# ProPrj_tp4056_charger_2026-03-09.net
KiCad netlist of a schematic drawn in EasyEDA Pro
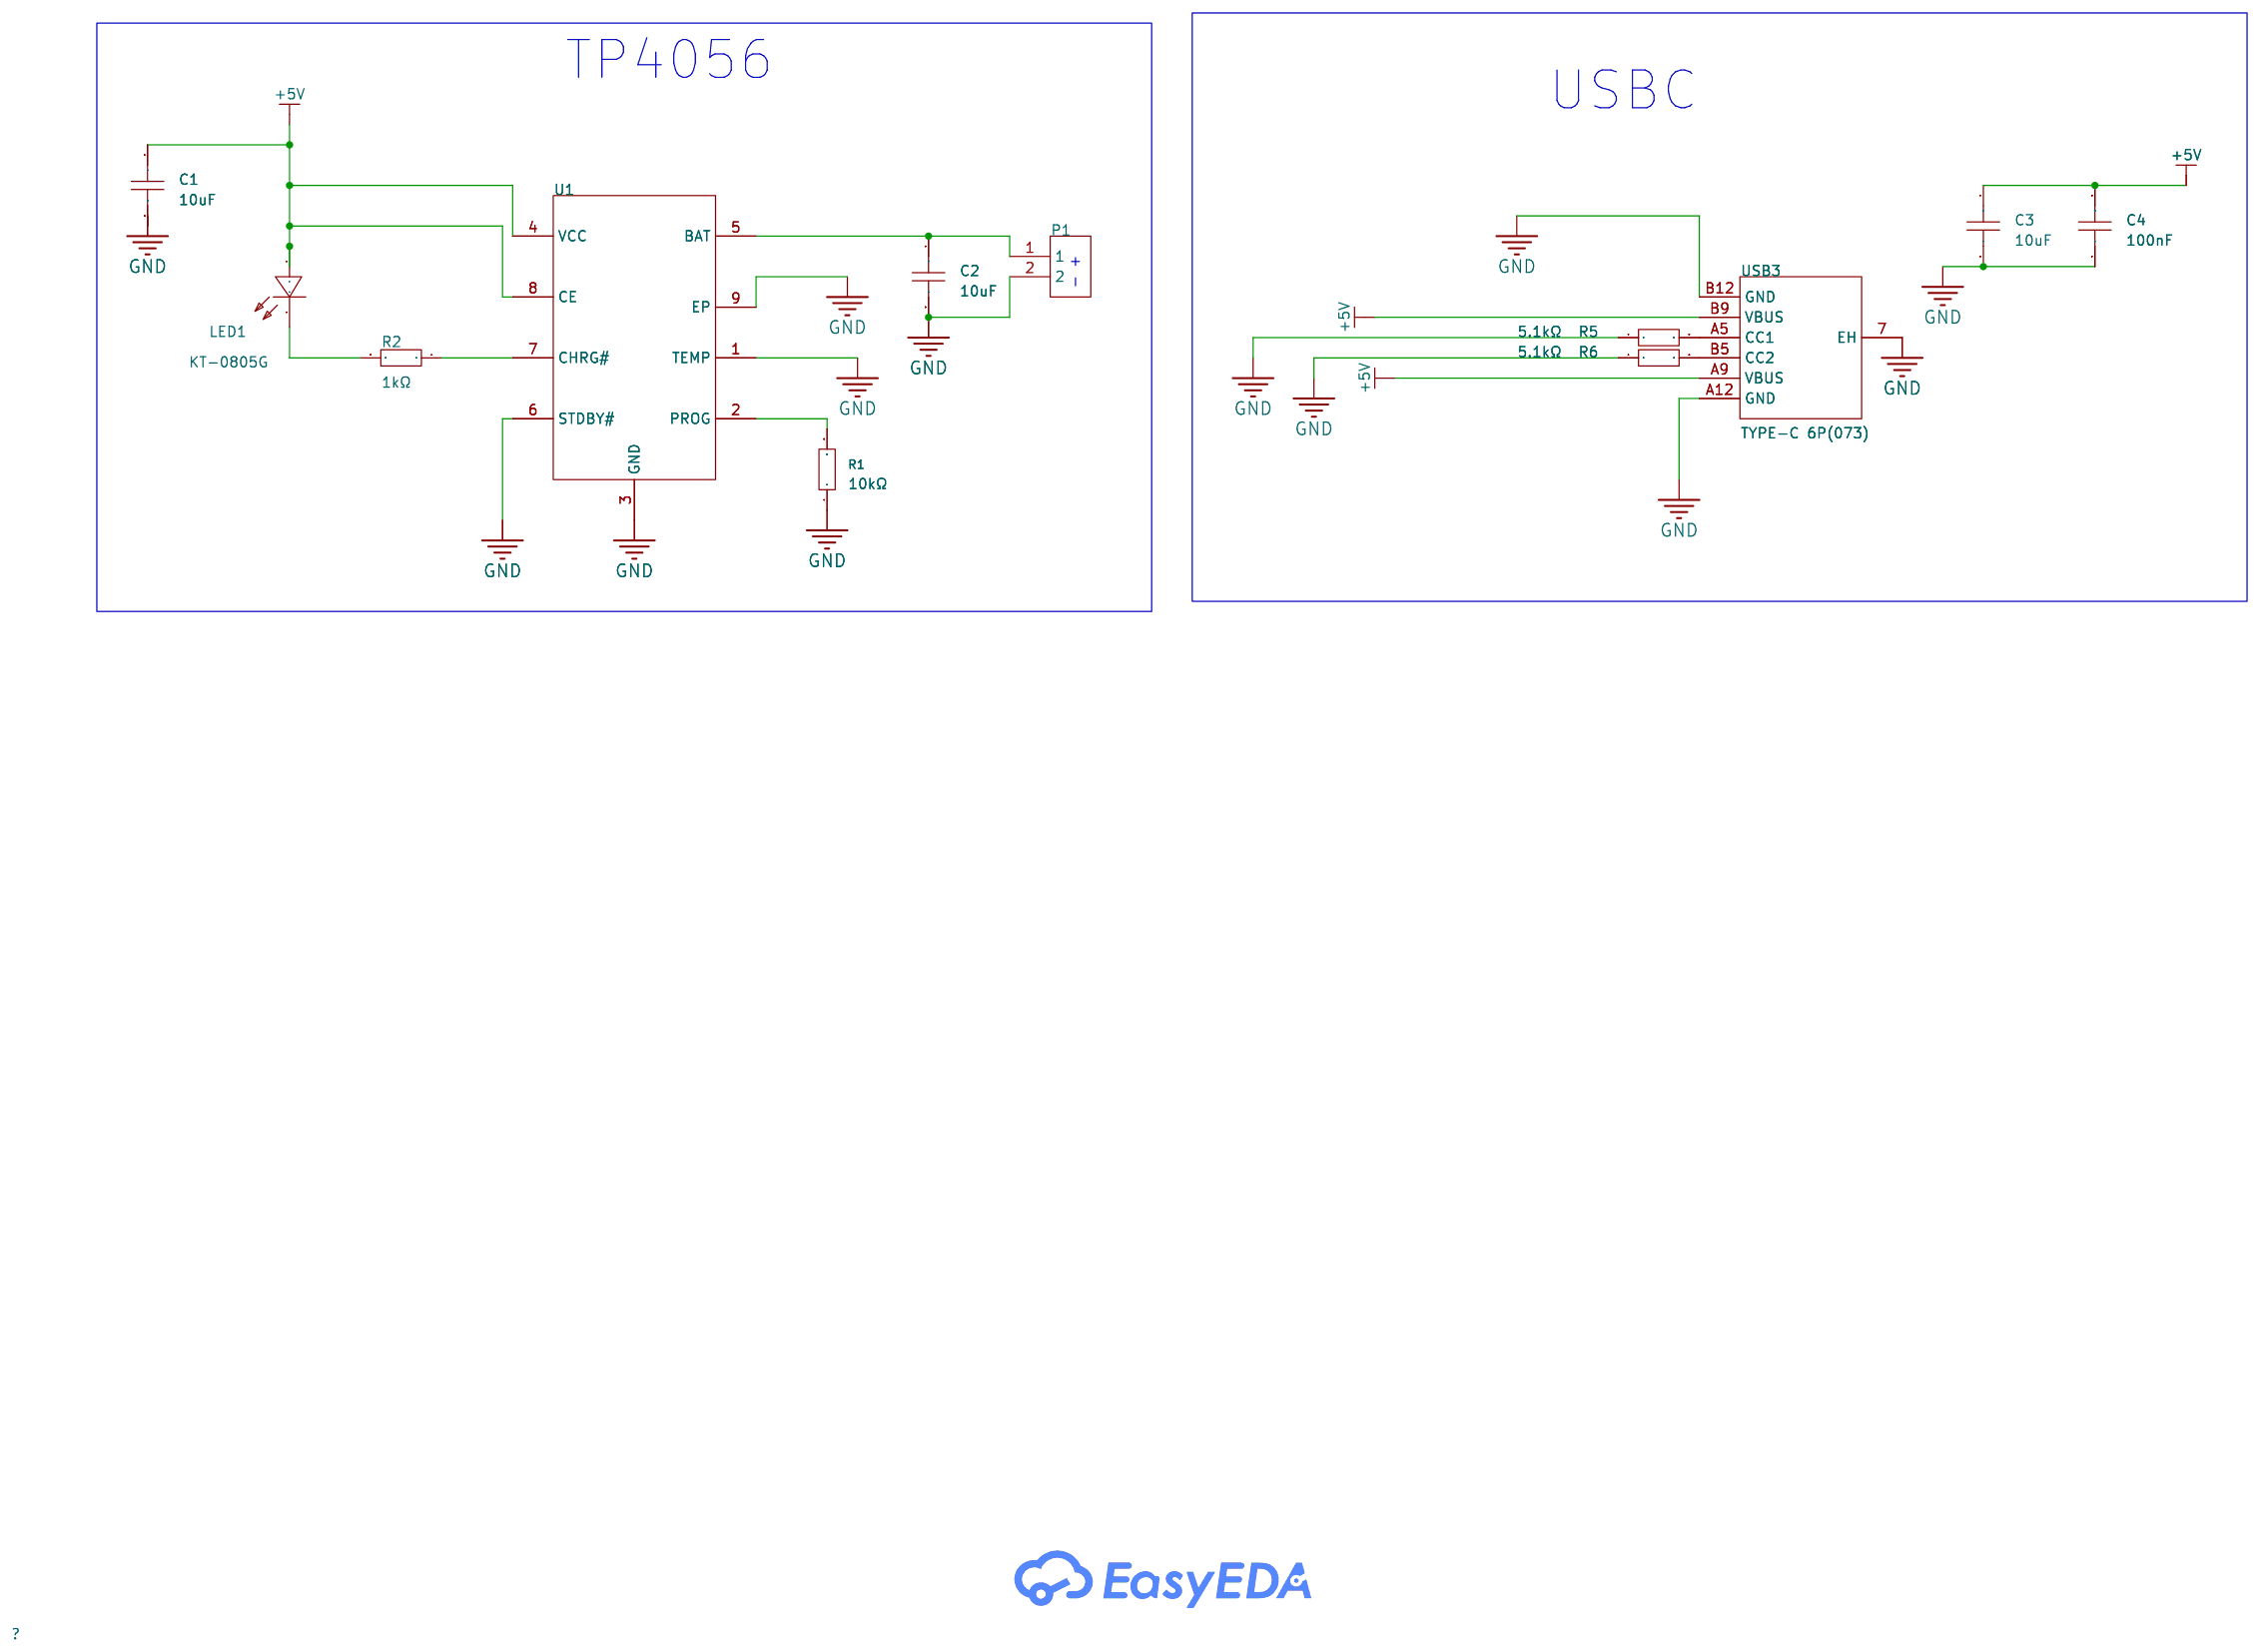
[diagram p0: schematic sheet]

(export (version "E")
  (design (tool "Eeschema 10.0.6"))
  (components
    (comp (ref "C1")
      (value "10uF")
      (footprint "easyedapro:C0805")
      (description "Capacitance:10uF Tolerance:±10% Tolerance:±10% Voltage Rating:25V Temperature Coefficient:X5R")
      (fields
        (field (name "Manufacturer Part") "CL21A106KAYNNNE")
        (field (name "Manufacturer") "SAMSUNG(三星)")
      )
      (libsource (lib "easyedapro") (part "CL21A106KAYNNNE"))
    )
    (comp (ref "C2")
      (value "10uF")
      (footprint "easyedapro:C0805")
      (description "Capacitance:10uF Tolerance:±10% Tolerance:±10% Voltage Rating:25V Temperature Coefficient:X5R")
      (fields
        (field (name "Manufacturer Part") "CL21A106KAYNNNE")
        (field (name "Manufacturer") "SAMSUNG(三星)")
      )
      (libsource (lib "easyedapro") (part "CL21A106KAYNNNE"))
    )
    (comp (ref "C3")
      (value "10uF")
      (footprint "easyedapro:C0805")
      (description "Capacitance:10uF Tolerance:±10% Tolerance:±10% Voltage Rating:25V Temperature Coefficient:X5R")
      (fields
        (field (name "Manufacturer Part") "CL21A106KAYNNNE")
        (field (name "Manufacturer") "SAMSUNG(三星)")
      )
      (libsource (lib "easyedapro") (part "CL21A106KAYNNNE"))
    )
    (comp (ref "C4")
      (value "100nF")
      (footprint "easyedapro:C0402")
      (description "Capacitance:100nF Tolerance:±10% Tolerance:±10% Voltage Rating:16V Temperature Coefficient:X7R")
      (fields
        (field (name "Manufacturer Part") "CL05B104KO5NNNC")
        (field (name "Manufacturer") "SAMSUNG(三星)")
      )
      (libsource (lib "easyedapro") (part "CL05B104KO5NNNC"))
    )
    (comp (ref "LED1")
      (value "KT-0805G")
      (footprint "easyedapro:LED0805-R-RD")
      (fields (field (name "Manufacturer") "KENTO"))
      (libsource (lib "easyedapro") (part "0805G (Green)"))
    )
    (comp (ref "P1")
      (value "WJ301V-5.0-02P-12-00A")
      (footprint "easyedapro:CONN-TH_2P-P5.00_WJ301V-5.00-2P")
      (fields (field (name "Manufacturer") "KANGNEX(康奈克斯电气)"))
      (libsource (lib "easyedapro") (part "WJ301V-5.0-2P"))
    )
    (comp (ref "R1")
      (value "10kΩ")
      (footprint "easyedapro:R1206")
      (fields
        (field (name "Manufacturer Part") "1206W4F1002T5E")
        (field (name "Manufacturer") "UNI-ROYAL(厚声)")
      )
      (libsource (lib "easyedapro") (part "1206W4F1002T5E"))
    )
    (comp (ref "R2")
      (value "1kΩ")
      (footprint "easyedapro:R0402")
      (fields
        (field (name "Manufacturer Part") "0402WGF1001TCE")
        (field (name "Manufacturer") "UNI-ROYAL(厚声)")
      )
      (libsource (lib "easyedapro") (part "0402WGF1001TCE"))
    )
    (comp (ref "R5")
      (value "5.1kΩ")
      (footprint "easyedapro:R0603")
      (fields
        (field (name "Manufacturer Part") "0603WAF5101T5E")
        (field (name "Manufacturer") "UNI-ROYAL(厚声)")
      )
      (libsource (lib "easyedapro") (part "0603WAF5101T5E"))
    )
    (comp (ref "R6")
      (value "5.1kΩ")
      (footprint "easyedapro:R0603")
      (fields
        (field (name "Manufacturer Part") "0603WAF5101T5E")
        (field (name "Manufacturer") "UNI-ROYAL(厚声)")
      )
      (libsource (lib "easyedapro") (part "0603WAF5101T5E"))
    )
    (comp (ref "U1")
      (value "TP4056-42-ESOP8")
      (footprint "easyedapro:ESOP-8_L4.9-W3.9-P1.27-LS6.0-BL-EP")
      (fields (field (name "Manufacturer") "TOPPOWER(南京拓微)"))
      (libsource (lib "easyedapro") (part "TP4056"))
    )
    (comp (ref "USB3")
      (value "TYPE-C 6P(073)")
      (footprint "easyedapro:TYPE-C-SMD_TYPE-C-6P-073")
      (fields (field (name "Manufacturer") "SHOU HAN(首韩)"))
      (libsource (lib "easyedapro") (part "TYPE-C 6P(073)"))
    )
  )
  (nets
    (net (code "1") (name "+5V") (class "Default")
      (node (ref "C1") (pin "1") (pinfunction "1_1") (pintype "unspecified"))
      (node (ref "C3") (pin "1") (pinfunction "1_1") (pintype "unspecified"))
      (node (ref "C4") (pin "2") (pinfunction "2_2") (pintype "unspecified"))
      (node (ref "LED1") (pin "1") (pinfunction "A_1") (pintype "unspecified"))
      (node (ref "U1") (pin "4") (pinfunction "VCC_4") (pintype "unspecified"))
      (node (ref "U1") (pin "8") (pinfunction "CE_8") (pintype "unspecified"))
      (node (ref "USB3") (pin "A9") (pinfunction "VBUS_A9") (pintype "unspecified"))
      (node (ref "USB3") (pin "B9") (pinfunction "VBUS_B9") (pintype "unspecified"))
    )
    (net (code "2") (name "GND") (class "Default")
      (node (ref "C1") (pin "2") (pinfunction "2_2") (pintype "unspecified"))
      (node (ref "C2") (pin "2") (pinfunction "2_2") (pintype "unspecified"))
      (node (ref "C3") (pin "2") (pinfunction "2_2") (pintype "unspecified"))
      (node (ref "C4") (pin "1") (pinfunction "1_1") (pintype "unspecified"))
      (node (ref "P1") (pin "2") (pinfunction "2_2") (pintype "unspecified"))
      (node (ref "R1") (pin "1") (pinfunction "1_1") (pintype "input"))
      (node (ref "R5") (pin "1") (pinfunction "1_1") (pintype "input"))
      (node (ref "R6") (pin "1") (pinfunction "1_1") (pintype "input"))
      (node (ref "U1") (pin "1") (pinfunction "TEMP_1") (pintype "unspecified"))
      (node (ref "U1") (pin "3") (pinfunction "GND_3") (pintype "unspecified"))
      (node (ref "U1") (pin "6") (pinfunction "STDBY#_6") (pintype "unspecified"))
      (node (ref "U1") (pin "9") (pinfunction "EP_9") (pintype "unspecified"))
      (node (ref "USB3") (pin "7") (pinfunction "EH_7") (pintype "unspecified"))
      (node (ref "USB3") (pin "A12") (pinfunction "GND_A12") (pintype "unspecified"))
      (node (ref "USB3") (pin "B12") (pinfunction "GND_B12") (pintype "unspecified"))
    )
    (net (code "3") (name "Net-(LED1-K)") (class "Default")
      (node (ref "LED1") (pin "2") (pinfunction "K_2") (pintype "unspecified"))
      (node (ref "R2") (pin "2") (pinfunction "2_2") (pintype "input"))
    )
    (net (code "4") (name "Net-(U1-BAT)") (class "Default")
      (node (ref "C2") (pin "1") (pinfunction "1_1") (pintype "unspecified"))
      (node (ref "P1") (pin "1") (pinfunction "1_1") (pintype "unspecified"))
      (node (ref "U1") (pin "5") (pinfunction "BAT_5") (pintype "unspecified"))
    )
    (net (code "5") (name "Net-(U1-CHRG#)") (class "Default")
      (node (ref "R2") (pin "1") (pinfunction "1_1") (pintype "input"))
      (node (ref "U1") (pin "7") (pinfunction "CHRG#_7") (pintype "unspecified"))
    )
    (net (code "6") (name "Net-(U1-PROG)") (class "Default")
      (node (ref "R1") (pin "2") (pinfunction "2_2") (pintype "input"))
      (node (ref "U1") (pin "2") (pinfunction "PROG_2") (pintype "unspecified"))
    )
    (net (code "7") (name "Net-(USB3-CC1)") (class "Default")
      (node (ref "R5") (pin "2") (pinfunction "2_2") (pintype "input"))
      (node (ref "USB3") (pin "A5") (pinfunction "CC1_A5") (pintype "unspecified"))
    )
    (net (code "8") (name "Net-(USB3-CC2)") (class "Default")
      (node (ref "R6") (pin "2") (pinfunction "2_2") (pintype "input"))
      (node (ref "USB3") (pin "B5") (pinfunction "CC2_B5") (pintype "unspecified"))
    )
  )
)
